# Output_Logic.net
KiCad netlist of a schematic drawn in EAGLE
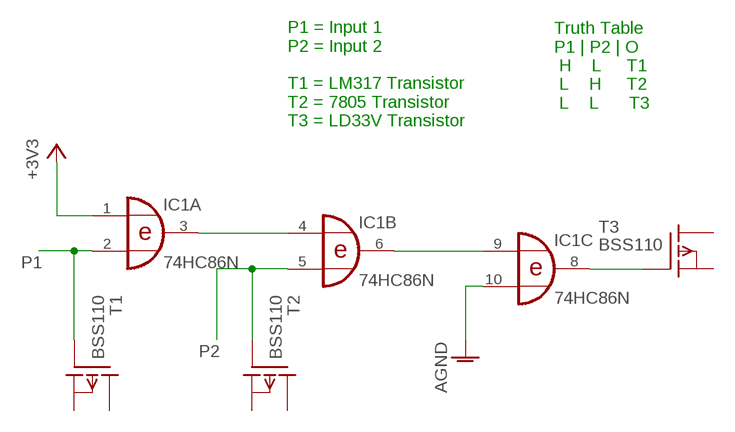
[diagram p0: schematic, sheet 1]

(export (version "E")
  (design (tool "Eeschema 10.0.6"))
  (components
    (comp (ref "IC1")
      (value "74HC86N")
      (footprint "eagle-import:DIL14")
      (libsource (lib "eagle-import") (part "7486NHC"))
    )
    (comp (ref "T1")
      (value "BSS110")
      (footprint "eagle-import:TO92")
      (libsource (lib "eagle-import") (part "BSS110"))
    )
    (comp (ref "T2")
      (value "BSS110")
      (footprint "eagle-import:TO92")
      (libsource (lib "eagle-import") (part "BSS110"))
    )
    (comp (ref "T3")
      (value "BSS110")
      (footprint "eagle-import:TO92")
      (libsource (lib "eagle-import") (part "BSS110"))
    )
  )
  (nets
    (net (code "1") (name "+3V3") (class "Default")
      (node (ref "IC1") (pin "1") (pinfunction "I0_1") (pintype "input"))
    )
    (net (code "2") (name "/P1") (class "Default")
      (node (ref "IC1") (pin "2") (pinfunction "I1_2") (pintype "input"))
      (node (ref "T1") (pin "2") (pinfunction "G_2") (pintype "passive"))
    )
    (net (code "3") (name "/P2") (class "Default")
      (node (ref "IC1") (pin "5") (pinfunction "I1_5") (pintype "input"))
      (node (ref "T2") (pin "2") (pinfunction "G_2") (pintype "passive"))
    )
    (net (code "4") (name "AGND") (class "Default")
      (node (ref "IC1") (pin "10") (pinfunction "I1_10") (pintype "input"))
    )
    (net (code "5") (name "Net-(IC1A-O)") (class "Default")
      (node (ref "IC1") (pin "3") (pinfunction "O_3") (pintype "output"))
      (node (ref "IC1") (pin "4") (pinfunction "I0_4") (pintype "input"))
    )
    (net (code "6") (name "Net-(IC1B-O)") (class "Default")
      (node (ref "IC1") (pin "6") (pinfunction "O_6") (pintype "output"))
      (node (ref "IC1") (pin "9") (pinfunction "I0_9") (pintype "input"))
    )
    (net (code "7") (name "Net-(IC1C-O)") (class "Default")
      (node (ref "IC1") (pin "8") (pinfunction "O_8") (pintype "output"))
      (node (ref "T3") (pin "2") (pinfunction "G_2") (pintype "passive"))
    )
    (net (code "8") (name "unconnected-(T1-D-Pad3)") (class "Default")
      (node (ref "T1") (pin "3") (pinfunction "D_3") (pintype "passive"))
    )
    (net (code "9") (name "unconnected-(T1-S-Pad1)") (class "Default")
      (node (ref "T1") (pin "1") (pinfunction "S_1") (pintype "passive"))
    )
    (net (code "10") (name "unconnected-(T2-D-Pad3)") (class "Default")
      (node (ref "T2") (pin "3") (pinfunction "D_3") (pintype "passive"))
    )
    (net (code "11") (name "unconnected-(T2-S-Pad1)") (class "Default")
      (node (ref "T2") (pin "1") (pinfunction "S_1") (pintype "passive"))
    )
    (net (code "12") (name "unconnected-(T3-D-Pad3)") (class "Default")
      (node (ref "T3") (pin "3") (pinfunction "D_3") (pintype "passive"))
    )
    (net (code "13") (name "unconnected-(T3-S-Pad1)") (class "Default")
      (node (ref "T3") (pin "1") (pinfunction "S_1") (pintype "passive"))
    )
  )
)
